# relay_driver.net
KiCad netlist of a schematic drawn in Altium Designer
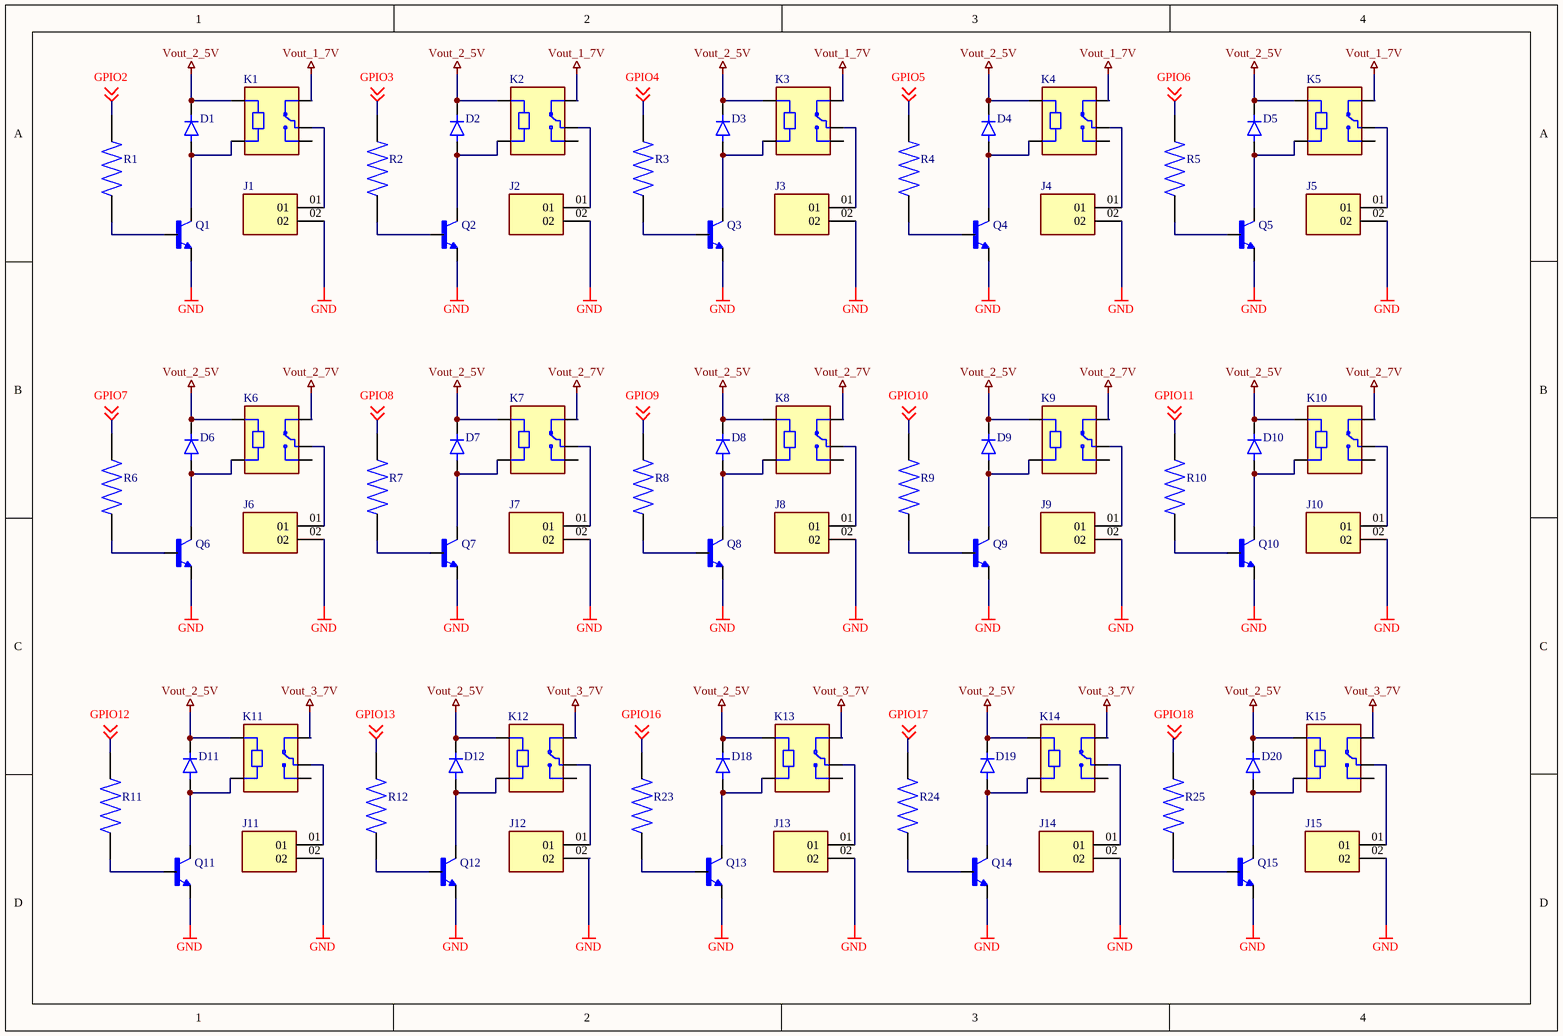
[diagram p0: relay_driver.SchDoc]

(export (version "E")
  (design (tool "Eeschema 10.0.6"))
  (components
    (comp (ref "D1")
      (value "FDLL4148")
      (footprint "DIOMELF3414N")
      (description "Diode Standard 100 V 200mA Surface Mount SOD-80")
      (fields (field (name "MF") "ON Semiconductor"))
      (libsource (lib "FDLL4148") (part "FDLL4148"))
    )
    (comp (ref "D2")
      (value "FDLL4148")
      (footprint "DIOMELF3414N")
      (description "Diode Standard 100 V 200mA Surface Mount SOD-80")
      (fields (field (name "MF") "ON Semiconductor"))
      (libsource (lib "FDLL4148") (part "FDLL4148"))
    )
    (comp (ref "D3")
      (value "FDLL4148")
      (footprint "DIOMELF3414N")
      (description "Diode Standard 100 V 200mA Surface Mount SOD-80")
      (fields (field (name "MF") "ON Semiconductor"))
      (libsource (lib "FDLL4148") (part "FDLL4148"))
    )
    (comp (ref "D4")
      (value "FDLL4148")
      (footprint "DIOMELF3414N")
      (description "Diode Standard 100 V 200mA Surface Mount SOD-80")
      (fields (field (name "MF") "ON Semiconductor"))
      (libsource (lib "FDLL4148") (part "FDLL4148"))
    )
    (comp (ref "D5")
      (value "FDLL4148")
      (footprint "DIOMELF3414N")
      (description "Diode Standard 100 V 200mA Surface Mount SOD-80")
      (fields (field (name "MF") "ON Semiconductor"))
      (libsource (lib "FDLL4148") (part "FDLL4148"))
    )
    (comp (ref "D6")
      (value "FDLL4148")
      (footprint "DIOMELF3414N")
      (description "Diode Standard 100 V 200mA Surface Mount SOD-80")
      (fields (field (name "MF") "ON Semiconductor"))
      (libsource (lib "FDLL4148") (part "FDLL4148"))
    )
    (comp (ref "D7")
      (value "FDLL4148")
      (footprint "DIOMELF3414N")
      (description "Diode Standard 100 V 200mA Surface Mount SOD-80")
      (fields (field (name "MF") "ON Semiconductor"))
      (libsource (lib "FDLL4148") (part "FDLL4148"))
    )
    (comp (ref "D8")
      (value "FDLL4148")
      (footprint "DIOMELF3414N")
      (description "Diode Standard 100 V 200mA Surface Mount SOD-80")
      (fields (field (name "MF") "ON Semiconductor"))
      (libsource (lib "FDLL4148") (part "FDLL4148"))
    )
    (comp (ref "D9")
      (value "FDLL4148")
      (footprint "DIOMELF3414N")
      (description "Diode Standard 100 V 200mA Surface Mount SOD-80")
      (fields (field (name "MF") "ON Semiconductor"))
      (libsource (lib "FDLL4148") (part "FDLL4148"))
    )
    (comp (ref "D10")
      (value "FDLL4148")
      (footprint "DIOMELF3414N")
      (description "Diode Standard 100 V 200mA Surface Mount SOD-80")
      (fields (field (name "MF") "ON Semiconductor"))
      (libsource (lib "FDLL4148") (part "FDLL4148"))
    )
    (comp (ref "D11")
      (value "FDLL4148")
      (footprint "DIOMELF3414N")
      (description "Diode Standard 100 V 200mA Surface Mount SOD-80")
      (fields (field (name "MF") "ON Semiconductor"))
      (libsource (lib "FDLL4148") (part "FDLL4148"))
    )
    (comp (ref "D12")
      (value "FDLL4148")
      (footprint "DIOMELF3414N")
      (description "Diode Standard 100 V 200mA Surface Mount SOD-80")
      (fields (field (name "MF") "ON Semiconductor"))
      (libsource (lib "FDLL4148") (part "FDLL4148"))
    )
    (comp (ref "D18")
      (value "FDLL4148")
      (footprint "DIOMELF3414N")
      (description "Diode Standard 100 V 200mA Surface Mount SOD-80")
      (fields (field (name "MF") "ON Semiconductor"))
      (libsource (lib "FDLL4148") (part "FDLL4148"))
    )
    (comp (ref "D19")
      (value "FDLL4148")
      (footprint "DIOMELF3414N")
      (description "Diode Standard 100 V 200mA Surface Mount SOD-80")
      (fields (field (name "MF") "ON Semiconductor"))
      (libsource (lib "FDLL4148") (part "FDLL4148"))
    )
    (comp (ref "D20")
      (value "FDLL4148")
      (footprint "DIOMELF3414N")
      (description "Diode Standard 100 V 200mA Surface Mount SOD-80")
      (fields (field (name "MF") "ON Semiconductor"))
      (libsource (lib "FDLL4148") (part "FDLL4148"))
    )
    (comp (ref "J1")
      (value "BBS-102-T-A")
      (footprint "SAMTEC_BBS-102-T-A")
      (fields (field (name "MF") "Samtec") (field (name "MP") "BBS102TA"))
      (libsource (lib "BBS-102-T-A") (part "BBS-102-T-A"))
    )
    (comp (ref "J2")
      (value "BBS-102-T-A")
      (footprint "SAMTEC_BBS-102-T-A")
      (fields (field (name "MF") "Samtec") (field (name "MP") "BBS102TA"))
      (libsource (lib "BBS-102-T-A") (part "BBS-102-T-A"))
    )
    (comp (ref "J3")
      (value "BBS-102-T-A")
      (footprint "SAMTEC_BBS-102-T-A")
      (fields (field (name "MF") "Samtec") (field (name "MP") "BBS102TA"))
      (libsource (lib "BBS-102-T-A") (part "BBS-102-T-A"))
    )
    (comp (ref "J4")
      (value "BBS-102-T-A")
      (footprint "SAMTEC_BBS-102-T-A")
      (fields (field (name "MF") "Samtec") (field (name "MP") "BBS102TA"))
      (libsource (lib "BBS-102-T-A") (part "BBS-102-T-A"))
    )
    (comp (ref "J5")
      (value "BBS-102-T-A")
      (footprint "SAMTEC_BBS-102-T-A")
      (fields (field (name "MF") "Samtec") (field (name "MP") "BBS102TA"))
      (libsource (lib "BBS-102-T-A") (part "BBS-102-T-A"))
    )
    (comp (ref "J6")
      (value "BBS-102-T-A")
      (footprint "SAMTEC_BBS-102-T-A")
      (fields (field (name "MF") "Samtec") (field (name "MP") "BBS102TA"))
      (libsource (lib "BBS-102-T-A") (part "BBS-102-T-A"))
    )
    (comp (ref "J7")
      (value "BBS-102-T-A")
      (footprint "SAMTEC_BBS-102-T-A")
      (fields (field (name "MF") "Samtec") (field (name "MP") "BBS102TA"))
      (libsource (lib "BBS-102-T-A") (part "BBS-102-T-A"))
    )
    (comp (ref "J8")
      (value "BBS-102-T-A")
      (footprint "SAMTEC_BBS-102-T-A")
      (fields (field (name "MF") "Samtec") (field (name "MP") "BBS102TA"))
      (libsource (lib "BBS-102-T-A") (part "BBS-102-T-A"))
    )
    (comp (ref "J9")
      (value "BBS-102-T-A")
      (footprint "SAMTEC_BBS-102-T-A")
      (fields (field (name "MF") "Samtec") (field (name "MP") "BBS102TA"))
      (libsource (lib "BBS-102-T-A") (part "BBS-102-T-A"))
    )
    (comp (ref "J10")
      (value "BBS-102-T-A")
      (footprint "SAMTEC_BBS-102-T-A")
      (fields (field (name "MF") "Samtec") (field (name "MP") "BBS102TA"))
      (libsource (lib "BBS-102-T-A") (part "BBS-102-T-A"))
    )
    (comp (ref "J11")
      (value "BBS-102-T-A")
      (footprint "SAMTEC_BBS-102-T-A")
      (fields (field (name "MF") "Samtec") (field (name "MP") "BBS102TA"))
      (libsource (lib "BBS-102-T-A") (part "BBS-102-T-A"))
    )
    (comp (ref "J12")
      (value "BBS-102-T-A")
      (footprint "SAMTEC_BBS-102-T-A")
      (fields (field (name "MF") "Samtec") (field (name "MP") "BBS102TA"))
      (libsource (lib "BBS-102-T-A") (part "BBS-102-T-A"))
    )
    (comp (ref "J13")
      (value "BBS-102-T-A")
      (footprint "SAMTEC_BBS-102-T-A")
      (fields (field (name "MF") "Samtec") (field (name "MP") "BBS102TA"))
      (libsource (lib "BBS-102-T-A") (part "BBS-102-T-A"))
    )
    (comp (ref "J14")
      (value "BBS-102-T-A")
      (footprint "SAMTEC_BBS-102-T-A")
      (fields (field (name "MF") "Samtec") (field (name "MP") "BBS102TA"))
      (libsource (lib "BBS-102-T-A") (part "BBS-102-T-A"))
    )
    (comp (ref "J15")
      (value "BBS-102-T-A")
      (footprint "SAMTEC_BBS-102-T-A")
      (fields (field (name "MF") "Samtec") (field (name "MP") "BBS102TA"))
      (libsource (lib "BBS-102-T-A") (part "BBS-102-T-A"))
    )
    (comp (ref "K1")
      (value "SRD-05VDC-SL-C")
      (footprint "RELAY_SRD-05VDC-SL-C")
      (fields (field (name "MF") "Songle Relay"))
      (libsource (lib "SRD-05VDC-SL-C") (part "SRD-05VDC-SL-C"))
    )
    (comp (ref "K2")
      (value "SRD-05VDC-SL-C")
      (footprint "RELAY_SRD-05VDC-SL-C")
      (fields (field (name "MF") "Songle Relay"))
      (libsource (lib "SRD-05VDC-SL-C") (part "SRD-05VDC-SL-C"))
    )
    (comp (ref "K3")
      (value "SRD-05VDC-SL-C")
      (footprint "RELAY_SRD-05VDC-SL-C")
      (fields (field (name "MF") "Songle Relay"))
      (libsource (lib "SRD-05VDC-SL-C") (part "SRD-05VDC-SL-C"))
    )
    (comp (ref "K4")
      (value "SRD-05VDC-SL-C")
      (footprint "RELAY_SRD-05VDC-SL-C")
      (fields (field (name "MF") "Songle Relay"))
      (libsource (lib "SRD-05VDC-SL-C") (part "SRD-05VDC-SL-C"))
    )
    (comp (ref "K5")
      (value "SRD-05VDC-SL-C")
      (footprint "RELAY_SRD-05VDC-SL-C")
      (fields (field (name "MF") "Songle Relay"))
      (libsource (lib "SRD-05VDC-SL-C") (part "SRD-05VDC-SL-C"))
    )
    (comp (ref "K6")
      (value "SRD-05VDC-SL-C")
      (footprint "RELAY_SRD-05VDC-SL-C")
      (fields (field (name "MF") "Songle Relay"))
      (libsource (lib "SRD-05VDC-SL-C") (part "SRD-05VDC-SL-C"))
    )
    (comp (ref "K7")
      (value "SRD-05VDC-SL-C")
      (footprint "RELAY_SRD-05VDC-SL-C")
      (fields (field (name "MF") "Songle Relay"))
      (libsource (lib "SRD-05VDC-SL-C") (part "SRD-05VDC-SL-C"))
    )
    (comp (ref "K8")
      (value "SRD-05VDC-SL-C")
      (footprint "RELAY_SRD-05VDC-SL-C")
      (fields (field (name "MF") "Songle Relay"))
      (libsource (lib "SRD-05VDC-SL-C") (part "SRD-05VDC-SL-C"))
    )
    (comp (ref "K9")
      (value "SRD-05VDC-SL-C")
      (footprint "RELAY_SRD-05VDC-SL-C")
      (fields (field (name "MF") "Songle Relay"))
      (libsource (lib "SRD-05VDC-SL-C") (part "SRD-05VDC-SL-C"))
    )
    (comp (ref "K10")
      (value "SRD-05VDC-SL-C")
      (footprint "RELAY_SRD-05VDC-SL-C")
      (fields (field (name "MF") "Songle Relay"))
      (libsource (lib "SRD-05VDC-SL-C") (part "SRD-05VDC-SL-C"))
    )
    (comp (ref "K11")
      (value "SRD-05VDC-SL-C")
      (footprint "RELAY_SRD-05VDC-SL-C")
      (fields (field (name "MF") "Songle Relay"))
      (libsource (lib "SRD-05VDC-SL-C") (part "SRD-05VDC-SL-C"))
    )
    (comp (ref "K12")
      (value "SRD-05VDC-SL-C")
      (footprint "RELAY_SRD-05VDC-SL-C")
      (fields (field (name "MF") "Songle Relay"))
      (libsource (lib "SRD-05VDC-SL-C") (part "SRD-05VDC-SL-C"))
    )
    (comp (ref "K13")
      (value "SRD-05VDC-SL-C")
      (footprint "RELAY_SRD-05VDC-SL-C")
      (fields (field (name "MF") "Songle Relay"))
      (libsource (lib "SRD-05VDC-SL-C") (part "SRD-05VDC-SL-C"))
    )
    (comp (ref "K14")
      (value "SRD-05VDC-SL-C")
      (footprint "RELAY_SRD-05VDC-SL-C")
      (fields (field (name "MF") "Songle Relay"))
      (libsource (lib "SRD-05VDC-SL-C") (part "SRD-05VDC-SL-C"))
    )
    (comp (ref "K15")
      (value "SRD-05VDC-SL-C")
      (footprint "RELAY_SRD-05VDC-SL-C")
      (fields (field (name "MF") "Songle Relay"))
      (libsource (lib "SRD-05VDC-SL-C") (part "SRD-05VDC-SL-C"))
    )
    (comp (ref "Q1")
      (value "BC817-40")
      (footprint "SOT95P240X120-3N")
      (description "BJT, SOT-23, 45V, 800mA, NPN, 0.31W, 150Â°C")
      (fields (field (name "MF") "Diotec Semiconductor"))
      (libsource (lib "BC817-40") (part "BC817-40"))
    )
    (comp (ref "Q2")
      (value "BC817-40")
      (footprint "SOT95P240X120-3N")
      (description "BJT, SOT-23, 45V, 800mA, NPN, 0.31W, 150Â°C")
      (fields (field (name "MF") "Diotec Semiconductor"))
      (libsource (lib "BC817-40") (part "BC817-40"))
    )
    (comp (ref "Q3")
      (value "BC817-40")
      (footprint "SOT95P240X120-3N")
      (description "BJT, SOT-23, 45V, 800mA, NPN, 0.31W, 150Â°C")
      (fields (field (name "MF") "Diotec Semiconductor"))
      (libsource (lib "BC817-40") (part "BC817-40"))
    )
    (comp (ref "Q4")
      (value "BC817-40")
      (footprint "SOT95P240X120-3N")
      (description "BJT, SOT-23, 45V, 800mA, NPN, 0.31W, 150Â°C")
      (fields (field (name "MF") "Diotec Semiconductor"))
      (libsource (lib "BC817-40") (part "BC817-40"))
    )
    (comp (ref "Q5")
      (value "BC817-40")
      (footprint "SOT95P240X120-3N")
      (description "BJT, SOT-23, 45V, 800mA, NPN, 0.31W, 150Â°C")
      (fields (field (name "MF") "Diotec Semiconductor"))
      (libsource (lib "BC817-40") (part "BC817-40"))
    )
    (comp (ref "Q6")
      (value "BC817-40")
      (footprint "SOT95P240X120-3N")
      (description "BJT, SOT-23, 45V, 800mA, NPN, 0.31W, 150Â°C")
      (fields (field (name "MF") "Diotec Semiconductor"))
      (libsource (lib "BC817-40") (part "BC817-40"))
    )
    (comp (ref "Q7")
      (value "BC817-40")
      (footprint "SOT95P240X120-3N")
      (description "BJT, SOT-23, 45V, 800mA, NPN, 0.31W, 150Â°C")
      (fields (field (name "MF") "Diotec Semiconductor"))
      (libsource (lib "BC817-40") (part "BC817-40"))
    )
    (comp (ref "Q8")
      (value "BC817-40")
      (footprint "SOT95P240X120-3N")
      (description "BJT, SOT-23, 45V, 800mA, NPN, 0.31W, 150Â°C")
      (fields (field (name "MF") "Diotec Semiconductor"))
      (libsource (lib "BC817-40") (part "BC817-40"))
    )
    (comp (ref "Q9")
      (value "BC817-40")
      (footprint "SOT95P240X120-3N")
      (description "BJT, SOT-23, 45V, 800mA, NPN, 0.31W, 150Â°C")
      (fields (field (name "MF") "Diotec Semiconductor"))
      (libsource (lib "BC817-40") (part "BC817-40"))
    )
    (comp (ref "Q10")
      (value "BC817-40")
      (footprint "SOT95P240X120-3N")
      (description "BJT, SOT-23, 45V, 800mA, NPN, 0.31W, 150Â°C")
      (fields (field (name "MF") "Diotec Semiconductor"))
      (libsource (lib "BC817-40") (part "BC817-40"))
    )
    (comp (ref "Q11")
      (value "BC817-40")
      (footprint "SOT95P240X120-3N")
      (description "BJT, SOT-23, 45V, 800mA, NPN, 0.31W, 150Â°C")
      (fields (field (name "MF") "Diotec Semiconductor"))
      (libsource (lib "BC817-40") (part "BC817-40"))
    )
    (comp (ref "Q12")
      (value "BC817-40")
      (footprint "SOT95P240X120-3N")
      (description "BJT, SOT-23, 45V, 800mA, NPN, 0.31W, 150Â°C")
      (fields (field (name "MF") "Diotec Semiconductor"))
      (libsource (lib "BC817-40") (part "BC817-40"))
    )
    (comp (ref "Q13")
      (value "BC817-40")
      (footprint "SOT95P240X120-3N")
      (description "BJT, SOT-23, 45V, 800mA, NPN, 0.31W, 150Â°C")
      (fields (field (name "MF") "Diotec Semiconductor"))
      (libsource (lib "BC817-40") (part "BC817-40"))
    )
    (comp (ref "Q14")
      (value "BC817-40")
      (footprint "SOT95P240X120-3N")
      (description "BJT, SOT-23, 45V, 800mA, NPN, 0.31W, 150Â°C")
      (fields (field (name "MF") "Diotec Semiconductor"))
      (libsource (lib "BC817-40") (part "BC817-40"))
    )
    (comp (ref "Q15")
      (value "BC817-40")
      (footprint "SOT95P240X120-3N")
      (description "BJT, SOT-23, 45V, 800mA, NPN, 0.31W, 150Â°C")
      (fields (field (name "MF") "Diotec Semiconductor"))
      (libsource (lib "BC817-40") (part "BC817-40"))
    )
    (comp (ref "R1")
      (value "ERJB3CFR15V")
      (footprint "RES_ERJB3CFR15V")
      (libsource (lib "ERJB3CFR15V") (part "ERJB3CFR15V"))
    )
    (comp (ref "R2")
      (value "ERJB3CFR15V")
      (footprint "RES_ERJB3CFR15V")
      (libsource (lib "ERJB3CFR15V") (part "ERJB3CFR15V"))
    )
    (comp (ref "R3")
      (value "ERJB3CFR15V")
      (footprint "RES_ERJB3CFR15V")
      (libsource (lib "ERJB3CFR15V") (part "ERJB3CFR15V"))
    )
    (comp (ref "R4")
      (value "ERJB3CFR15V")
      (footprint "RES_ERJB3CFR15V")
      (libsource (lib "ERJB3CFR15V") (part "ERJB3CFR15V"))
    )
    (comp (ref "R5")
      (value "ERJB3CFR15V")
      (footprint "RES_ERJB3CFR15V")
      (libsource (lib "ERJB3CFR15V") (part "ERJB3CFR15V"))
    )
    (comp (ref "R6")
      (value "ERJB3CFR15V")
      (footprint "RES_ERJB3CFR15V")
      (libsource (lib "ERJB3CFR15V") (part "ERJB3CFR15V"))
    )
    (comp (ref "R7")
      (value "ERJB3CFR15V")
      (footprint "RES_ERJB3CFR15V")
      (libsource (lib "ERJB3CFR15V") (part "ERJB3CFR15V"))
    )
    (comp (ref "R8")
      (value "ERJB3CFR15V")
      (footprint "RES_ERJB3CFR15V")
      (libsource (lib "ERJB3CFR15V") (part "ERJB3CFR15V"))
    )
    (comp (ref "R9")
      (value "ERJB3CFR15V")
      (footprint "RES_ERJB3CFR15V")
      (libsource (lib "ERJB3CFR15V") (part "ERJB3CFR15V"))
    )
    (comp (ref "R10")
      (value "ERJB3CFR15V")
      (footprint "RES_ERJB3CFR15V")
      (libsource (lib "ERJB3CFR15V") (part "ERJB3CFR15V"))
    )
    (comp (ref "R11")
      (value "ERJB3CFR15V")
      (footprint "RES_ERJB3CFR15V")
      (libsource (lib "ERJB3CFR15V") (part "ERJB3CFR15V"))
    )
    (comp (ref "R12")
      (value "ERJB3CFR15V")
      (footprint "RES_ERJB3CFR15V")
      (libsource (lib "ERJB3CFR15V") (part "ERJB3CFR15V"))
    )
    (comp (ref "R23")
      (value "ERJB3CFR15V")
      (footprint "RES_ERJB3CFR15V")
      (libsource (lib "ERJB3CFR15V") (part "ERJB3CFR15V"))
    )
    (comp (ref "R24")
      (value "ERJB3CFR15V")
      (footprint "RES_ERJB3CFR15V")
      (libsource (lib "ERJB3CFR15V") (part "ERJB3CFR15V"))
    )
    (comp (ref "R25")
      (value "ERJB3CFR15V")
      (footprint "RES_ERJB3CFR15V")
      (libsource (lib "ERJB3CFR15V") (part "ERJB3CFR15V"))
    )
  )
  (nets
    (net (code "1") (name "GND") (class "Default")
      (node (ref "J1") (pin "02") (pinfunction "02_02") (pintype "passive"))
      (node (ref "J10") (pin "02") (pinfunction "02_02") (pintype "passive"))
      (node (ref "J11") (pin "02") (pinfunction "02_02") (pintype "passive"))
      (node (ref "J12") (pin "02") (pinfunction "02_02") (pintype "passive"))
      (node (ref "J13") (pin "02") (pinfunction "02_02") (pintype "passive"))
      (node (ref "J14") (pin "02") (pinfunction "02_02") (pintype "passive"))
      (node (ref "J15") (pin "02") (pinfunction "02_02") (pintype "passive"))
      (node (ref "J2") (pin "02") (pinfunction "02_02") (pintype "passive"))
      (node (ref "J3") (pin "02") (pinfunction "02_02") (pintype "passive"))
      (node (ref "J4") (pin "02") (pinfunction "02_02") (pintype "passive"))
      (node (ref "J5") (pin "02") (pinfunction "02_02") (pintype "passive"))
      (node (ref "J6") (pin "02") (pinfunction "02_02") (pintype "passive"))
      (node (ref "J7") (pin "02") (pinfunction "02_02") (pintype "passive"))
      (node (ref "J8") (pin "02") (pinfunction "02_02") (pintype "passive"))
      (node (ref "J9") (pin "02") (pinfunction "02_02") (pintype "passive"))
      (node (ref "Q1") (pin "2") (pinfunction "E_2") (pintype "passive"))
      (node (ref "Q10") (pin "2") (pinfunction "E_2") (pintype "passive"))
      (node (ref "Q11") (pin "2") (pinfunction "E_2") (pintype "passive"))
      (node (ref "Q12") (pin "2") (pinfunction "E_2") (pintype "passive"))
      (node (ref "Q13") (pin "2") (pinfunction "E_2") (pintype "passive"))
      (node (ref "Q14") (pin "2") (pinfunction "E_2") (pintype "passive"))
      (node (ref "Q15") (pin "2") (pinfunction "E_2") (pintype "passive"))
      (node (ref "Q2") (pin "2") (pinfunction "E_2") (pintype "passive"))
      (node (ref "Q3") (pin "2") (pinfunction "E_2") (pintype "passive"))
      (node (ref "Q4") (pin "2") (pinfunction "E_2") (pintype "passive"))
      (node (ref "Q5") (pin "2") (pinfunction "E_2") (pintype "passive"))
      (node (ref "Q6") (pin "2") (pinfunction "E_2") (pintype "passive"))
      (node (ref "Q7") (pin "2") (pinfunction "E_2") (pintype "passive"))
      (node (ref "Q8") (pin "2") (pinfunction "E_2") (pintype "passive"))
      (node (ref "Q9") (pin "2") (pinfunction "E_2") (pintype "passive"))
    )
    (net (code "2") (name "GPIO2") (class "Default")
      (node (ref "R1") (pin "2") (pinfunction "2_2") (pintype "passive"))
    )
    (net (code "3") (name "GPIO3") (class "Default")
      (node (ref "R2") (pin "2") (pinfunction "2_2") (pintype "passive"))
    )
    (net (code "4") (name "GPIO4") (class "Default")
      (node (ref "R3") (pin "2") (pinfunction "2_2") (pintype "passive"))
    )
    (net (code "5") (name "GPIO5") (class "Default")
      (node (ref "R4") (pin "2") (pinfunction "2_2") (pintype "passive"))
    )
    (net (code "6") (name "GPIO6") (class "Default")
      (node (ref "R5") (pin "2") (pinfunction "2_2") (pintype "passive"))
    )
    (net (code "7") (name "GPIO7") (class "Default")
      (node (ref "R6") (pin "2") (pinfunction "2_2") (pintype "passive"))
    )
    (net (code "8") (name "GPIO8") (class "Default")
      (node (ref "R7") (pin "2") (pinfunction "2_2") (pintype "passive"))
    )
    (net (code "9") (name "GPIO9") (class "Default")
      (node (ref "R8") (pin "2") (pinfunction "2_2") (pintype "passive"))
    )
    (net (code "10") (name "GPIO10") (class "Default")
      (node (ref "R9") (pin "2") (pinfunction "2_2") (pintype "passive"))
    )
    (net (code "11") (name "GPIO11") (class "Default")
      (node (ref "R10") (pin "2") (pinfunction "2_2") (pintype "passive"))
    )
    (net (code "12") (name "GPIO12") (class "Default")
      (node (ref "R11") (pin "2") (pinfunction "2_2") (pintype "passive"))
    )
    (net (code "13") (name "GPIO13") (class "Default")
      (node (ref "R12") (pin "2") (pinfunction "2_2") (pintype "passive"))
    )
    (net (code "14") (name "GPIO16") (class "Default")
      (node (ref "R23") (pin "2") (pinfunction "2_2") (pintype "passive"))
    )
    (net (code "15") (name "GPIO17") (class "Default")
      (node (ref "R24") (pin "2") (pinfunction "2_2") (pintype "passive"))
    )
    (net (code "16") (name "GPIO18") (class "Default")
      (node (ref "R25") (pin "2") (pinfunction "2_2") (pintype "passive"))
    )
    (net (code "17") (name "Net-(J1-Pad01)") (class "Default")
      (node (ref "J1") (pin "01") (pinfunction "01_01") (pintype "passive"))
      (node (ref "K1") (pin "COM") (pinfunction "COM_COM") (pintype "passive"))
    )
    (net (code "18") (name "Net-(J2-Pad01)") (class "Default")
      (node (ref "J2") (pin "01") (pinfunction "01_01") (pintype "passive"))
      (node (ref "K2") (pin "COM") (pinfunction "COM_COM") (pintype "passive"))
    )
    (net (code "19") (name "Net-(J3-Pad01)") (class "Default")
      (node (ref "J3") (pin "01") (pinfunction "01_01") (pintype "passive"))
      (node (ref "K3") (pin "COM") (pinfunction "COM_COM") (pintype "passive"))
    )
    (net (code "20") (name "Net-(J4-Pad01)") (class "Default")
      (node (ref "J4") (pin "01") (pinfunction "01_01") (pintype "passive"))
      (node (ref "K4") (pin "COM") (pinfunction "COM_COM") (pintype "passive"))
    )
    (net (code "21") (name "Net-(J5-Pad01)") (class "Default")
      (node (ref "J5") (pin "01") (pinfunction "01_01") (pintype "passive"))
      (node (ref "K5") (pin "COM") (pinfunction "COM_COM") (pintype "passive"))
    )
    (net (code "22") (name "Net-(J6-Pad01)") (class "Default")
      (node (ref "J6") (pin "01") (pinfunction "01_01") (pintype "passive"))
      (node (ref "K6") (pin "COM") (pinfunction "COM_COM") (pintype "passive"))
    )
    (net (code "23") (name "Net-(J7-Pad01)") (class "Default")
      (node (ref "J7") (pin "01") (pinfunction "01_01") (pintype "passive"))
      (node (ref "K7") (pin "COM") (pinfunction "COM_COM") (pintype "passive"))
    )
    (net (code "24") (name "Net-(J8-Pad01)") (class "Default")
      (node (ref "J8") (pin "01") (pinfunction "01_01") (pintype "passive"))
      (node (ref "K8") (pin "COM") (pinfunction "COM_COM") (pintype "passive"))
    )
    (net (code "25") (name "Net-(J9-Pad01)") (class "Default")
      (node (ref "J9") (pin "01") (pinfunction "01_01") (pintype "passive"))
      (node (ref "K9") (pin "COM") (pinfunction "COM_COM") (pintype "passive"))
    )
    (net (code "26") (name "Net-(J10-Pad01)") (class "Default")
      (node (ref "J10") (pin "01") (pinfunction "01_01") (pintype "passive"))
      (node (ref "K10") (pin "COM") (pinfunction "COM_COM") (pintype "passive"))
    )
    (net (code "27") (name "Net-(J11-Pad01)") (class "Default")
      (node (ref "J11") (pin "01") (pinfunction "01_01") (pintype "passive"))
      (node (ref "K11") (pin "COM") (pinfunction "COM_COM") (pintype "passive"))
    )
    (net (code "28") (name "Net-(J12-Pad01)") (class "Default")
      (node (ref "J12") (pin "01") (pinfunction "01_01") (pintype "passive"))
      (node (ref "K12") (pin "COM") (pinfunction "COM_COM") (pintype "passive"))
    )
    (net (code "29") (name "Net-(J13-Pad01)") (class "Default")
      (node (ref "J13") (pin "01") (pinfunction "01_01") (pintype "passive"))
      (node (ref "K13") (pin "COM") (pinfunction "COM_COM") (pintype "passive"))
    )
    (net (code "30") (name "Net-(J14-Pad01)") (class "Default")
      (node (ref "J14") (pin "01") (pinfunction "01_01") (pintype "passive"))
      (node (ref "K14") (pin "COM") (pinfunction "COM_COM") (pintype "passive"))
    )
    (net (code "31") (name "Net-(J15-Pad01)") (class "Default")
      (node (ref "J15") (pin "01") (pinfunction "01_01") (pintype "passive"))
      (node (ref "K15") (pin "COM") (pinfunction "COM_COM") (pintype "passive"))
    )
    (net (code "32") (name "Net-(Q1-B)") (class "Default")
      (node (ref "Q1") (pin "1") (pinfunction "B_1") (pintype "passive"))
      (node (ref "R1") (pin "1") (pinfunction "1_1") (pintype "passive"))
    )
    (net (code "33") (name "Net-(Q1-C)") (class "Default")
      (node (ref "D1") (pin "A") (pinfunction "A_A") (pintype "passive"))
      (node (ref "K1") (pin "A1") (pinfunction "A1_A1") (pintype "passive"))
      (node (ref "Q1") (pin "3") (pinfunction "C_3") (pintype "passive"))
    )
    (net (code "34") (name "Net-(Q2-B)") (class "Default")
      (node (ref "Q2") (pin "1") (pinfunction "B_1") (pintype "passive"))
      (node (ref "R2") (pin "1") (pinfunction "1_1") (pintype "passive"))
    )
    (net (code "35") (name "Net-(Q2-C)") (class "Default")
      (node (ref "D2") (pin "A") (pinfunction "A_A") (pintype "passive"))
      (node (ref "K2") (pin "A1") (pinfunction "A1_A1") (pintype "passive"))
      (node (ref "Q2") (pin "3") (pinfunction "C_3") (pintype "passive"))
    )
    (net (code "36") (name "Net-(Q3-B)") (class "Default")
      (node (ref "Q3") (pin "1") (pinfunction "B_1") (pintype "passive"))
      (node (ref "R3") (pin "1") (pinfunction "1_1") (pintype "passive"))
    )
    (net (code "37") (name "Net-(Q3-C)") (class "Default")
      (node (ref "D3") (pin "A") (pinfunction "A_A") (pintype "passive"))
      (node (ref "K3") (pin "A1") (pinfunction "A1_A1") (pintype "passive"))
      (node (ref "Q3") (pin "3") (pinfunction "C_3") (pintype "passive"))
    )
    (net (code "38") (name "Net-(Q4-B)") (class "Default")
      (node (ref "Q4") (pin "1") (pinfunction "B_1") (pintype "passive"))
      (node (ref "R4") (pin "1") (pinfunction "1_1") (pintype "passive"))
    )
    (net (code "39") (name "Net-(Q4-C)") (class "Default")
      (node (ref "D4") (pin "A") (pinfunction "A_A") (pintype "passive"))
      (node (ref "K4") (pin "A1") (pinfunction "A1_A1") (pintype "passive"))
      (node (ref "Q4") (pin "3") (pinfunction "C_3") (pintype "passive"))
    )
    (net (code "40") (name "Net-(Q5-B)") (class "Default")
      (node (ref "Q5") (pin "1") (pinfunction "B_1") (pintype "passive"))
      (node (ref "R5") (pin "1") (pinfunction "1_1") (pintype "passive"))
    )
    (net (code "41") (name "Net-(Q5-C)") (class "Default")
      (node (ref "D5") (pin "A") (pinfunction "A_A") (pintype "passive"))
      (node (ref "K5") (pin "A1") (pinfunction "A1_A1") (pintype "passive"))
      (node (ref "Q5") (pin "3") (pinfunction "C_3") (pintype "passive"))
    )
    (net (code "42") (name "Net-(Q6-B)") (class "Default")
      (node (ref "Q6") (pin "1") (pinfunction "B_1") (pintype "passive"))
      (node (ref "R6") (pin "1") (pinfunction "1_1") (pintype "passive"))
    )
    (net (code "43") (name "Net-(Q6-C)") (class "Default")
      (node (ref "D6") (pin "A") (pinfunction "A_A") (pintype "passive"))
      (node (ref "K6") (pin "A1") (pinfunction "A1_A1") (pintype "passive"))
      (node (ref "Q6") (pin "3") (pinfunction "C_3") (pintype "passive"))
    )
    (net (code "44") (name "Net-(Q7-B)") (class "Default")
      (node (ref "Q7") (pin "1") (pinfunction "B_1") (pintype "passive"))
      (node (ref "R7") (pin "1") (pinfunction "1_1") (pintype "passive"))
    )
    (net (code "45") (name "Net-(Q7-C)") (class "Default")
      (node (ref "D7") (pin "A") (pinfunction "A_A") (pintype "passive"))
      (node (ref "K7") (pin "A1") (pinfunction "A1_A1") (pintype "passive"))
      (node (ref "Q7") (pin "3") (pinfunction "C_3") (pintype "passive"))
    )
    (net (code "46") (name "Net-(Q8-B)") (class "Default")
      (node (ref "Q8") (pin "1") (pinfunction "B_1") (pintype "passive"))
      (node (ref "R8") (pin "1") (pinfunction "1_1") (pintype "passive"))
    )
    (net (code "47") (name "Net-(Q8-C)") (class "Default")
      (node (ref "D8") (pin "A") (pinfunction "A_A") (pintype "passive"))
      (node (ref "K8") (pin "A1") (pinfunction "A1_A1") (pintype "passive"))
      (node (ref "Q8") (pin "3") (pinfunction "C_3") (pintype "passive"))
    )
    (net (code "48") (name "Net-(Q9-B)") (class "Default")
      (node (ref "Q9") (pin "1") (pinfunction "B_1") (pintype "passive"))
      (node (ref "R9") (pin "1") (pinfunction "1_1") (pintype "passive"))
    )
    (net (code "49") (name "Net-(Q9-C)") (class "Default")
      (node (ref "D9") (pin "A") (pinfunction "A_A") (pintype "passive"))
      (node (ref "K9") (pin "A1") (pinfunction "A1_A1") (pintype "passive"))
      (node (ref "Q9") (pin "3") (pinfunction "C_3") (pintype "passive"))
    )
    (net (code "50") (name "Net-(Q10-B)") (class "Default")
      (node (ref "Q10") (pin "1") (pinfunction "B_1") (pintype "passive"))
      (node (ref "R10") (pin "1") (pinfunction "1_1") (pintype "passive"))
    )
    (net (code "51") (name "Net-(Q10-C)") (class "Default")
      (node (ref "D10") (pin "A") (pinfunction "A_A") (pintype "passive"))
      (node (ref "K10") (pin "A1") (pinfunction "A1_A1") (pintype "passive"))
      (node (ref "Q10") (pin "3") (pinfunction "C_3") (pintype "passive"))
    )
    (net (code "52") (name "Net-(Q11-B)") (class "Default")
      (node (ref "Q11") (pin "1") (pinfunction "B_1") (pintype "passive"))
      (node (ref "R11") (pin "1") (pinfunction "1_1") (pintype "passive"))
    )
    (net (code "53") (name "Net-(Q11-C)") (class "Default")
      (node (ref "D11") (pin "A") (pinfunction "A_A") (pintype "passive"))
      (node (ref "K11") (pin "A1") (pinfunction "A1_A1") (pintype "passive"))
      (node (ref "Q11") (pin "3") (pinfunction "C_3") (pintype "passive"))
    )
    (net (code "54") (name "Net-(Q12-B)") (class "Default")
      (node (ref "Q12") (pin "1") (pinfunction "B_1") (pintype "passive"))
      (node (ref "R12") (pin "1") (pinfunction "1_1") (pintype "passive"))
    )
    (net (code "55") (name "Net-(Q12-C)") (class "Default")
      (node (ref "D12") (pin "A") (pinfunction "A_A") (pintype "passive"))
      (node (ref "K12") (pin "A1") (pinfunction "A1_A1") (pintype "passive"))
      (node (ref "Q12") (pin "3") (pinfunction "C_3") (pintype "passive"))
    )
    (net (code "56") (name "Net-(Q13-B)") (class "Default")
      (node (ref "Q13") (pin "1") (pinfunction "B_1") (pintype "passive"))
      (node (ref "R23") (pin "1") (pinfunction "1_1") (pintype "passive"))
    )
    (net (code "57") (name "Net-(Q13-C)") (class "Default")
      (node (ref "D18") (pin "A") (pinfunction "A_A") (pintype "passive"))
      (node (ref "K13") (pin "A1") (pinfunction "A1_A1") (pintype "passive"))
      (node (ref "Q13") (pin "3") (pinfunction "C_3") (pintype "passive"))
    )
    (net (code "58") (name "Net-(Q14-B)") (class "Default")
      (node (ref "Q14") (pin "1") (pinfunction "B_1") (pintype "passive"))
      (node (ref "R24") (pin "1") (pinfunction "1_1") (pintype "passive"))
    )
    (net (code "59") (name "Net-(Q14-C)") (class "Default")
      (node (ref "D19") (pin "A") (pinfunction "A_A") (pintype "passive"))
      (node (ref "K14") (pin "A1") (pinfunction "A1_A1") (pintype "passive"))
      (node (ref "Q14") (pin "3") (pinfunction "C_3") (pintype "passive"))
    )
    (net (code "60") (name "Net-(Q15-B)") (class "Default")
      (node (ref "Q15") (pin "1") (pinfunction "B_1") (pintype "passive"))
      (node (ref "R25") (pin "1") (pinfunction "1_1") (pintype "passive"))
    )
    (net (code "61") (name "Net-(Q15-C)") (class "Default")
      (node (ref "D20") (pin "A") (pinfunction "A_A") (pintype "passive"))
      (node (ref "K15") (pin "A1") (pinfunction "A1_A1") (pintype "passive"))
      (node (ref "Q15") (pin "3") (pinfunction "C_3") (pintype "passive"))
    )
    (net (code "62") (name "Vout_1_7V") (class "Default")
      (node (ref "K1") (pin "NC") (pinfunction "NC_NC") (pintype "passive"))
      (node (ref "K2") (pin "NC") (pinfunction "NC_NC") (pintype "passive"))
      (node (ref "K3") (pin "NC") (pinfunction "NC_NC") (pintype "passive"))
      (node (ref "K4") (pin "NC") (pinfunction "NC_NC") (pintype "passive"))
      (node (ref "K5") (pin "NC") (pinfunction "NC_NC") (pintype "passive"))
    )
    (net (code "63") (name "Vout_2_5V") (class "Default")
      (node (ref "D1") (pin "C") (pinfunction "C_C") (pintype "passive"))
      (node (ref "D10") (pin "C") (pinfunction "C_C") (pintype "passive"))
      (node (ref "D11") (pin "C") (pinfunction "C_C") (pintype "passive"))
      (node (ref "D12") (pin "C") (pinfunction "C_C") (pintype "passive"))
      (node (ref "D18") (pin "C") (pinfunction "C_C") (pintype "passive"))
      (node (ref "D19") (pin "C") (pinfunction "C_C") (pintype "passive"))
      (node (ref "D2") (pin "C") (pinfunction "C_C") (pintype "passive"))
      (node (ref "D20") (pin "C") (pinfunction "C_C") (pintype "passive"))
      (node (ref "D3") (pin "C") (pinfunction "C_C") (pintype "passive"))
      (node (ref "D4") (pin "C") (pinfunction "C_C") (pintype "passive"))
      (node (ref "D5") (pin "C") (pinfunction "C_C") (pintype "passive"))
      (node (ref "D6") (pin "C") (pinfunction "C_C") (pintype "passive"))
      (node (ref "D7") (pin "C") (pinfunction "C_C") (pintype "passive"))
      (node (ref "D8") (pin "C") (pinfunction "C_C") (pintype "passive"))
      (node (ref "D9") (pin "C") (pinfunction "C_C") (pintype "passive"))
      (node (ref "K1") (pin "A2") (pinfunction "A2_A2") (pintype "passive"))
      (node (ref "K10") (pin "A2") (pinfunction "A2_A2") (pintype "passive"))
      (node (ref "K11") (pin "A2") (pinfunction "A2_A2") (pintype "passive"))
      (node (ref "K12") (pin "A2") (pinfunction "A2_A2") (pintype "passive"))
      (node (ref "K13") (pin "A2") (pinfunction "A2_A2") (pintype "passive"))
      (node (ref "K14") (pin "A2") (pinfunction "A2_A2") (pintype "passive"))
      (node (ref "K15") (pin "A2") (pinfunction "A2_A2") (pintype "passive"))
      (node (ref "K2") (pin "A2") (pinfunction "A2_A2") (pintype "passive"))
      (node (ref "K3") (pin "A2") (pinfunction "A2_A2") (pintype "passive"))
      (node (ref "K4") (pin "A2") (pinfunction "A2_A2") (pintype "passive"))
      (node (ref "K5") (pin "A2") (pinfunction "A2_A2") (pintype "passive"))
      (node (ref "K6") (pin "A2") (pinfunction "A2_A2") (pintype "passive"))
      (node (ref "K7") (pin "A2") (pinfunction "A2_A2") (pintype "passive"))
      (node (ref "K8") (pin "A2") (pinfunction "A2_A2") (pintype "passive"))
      (node (ref "K9") (pin "A2") (pinfunction "A2_A2") (pintype "passive"))
    )
    (net (code "64") (name "Vout_2_7V") (class "Default")
      (node (ref "K10") (pin "NC") (pinfunction "NC_NC") (pintype "passive"))
      (node (ref "K6") (pin "NC") (pinfunction "NC_NC") (pintype "passive"))
      (node (ref "K7") (pin "NC") (pinfunction "NC_NC") (pintype "passive"))
      (node (ref "K8") (pin "NC") (pinfunction "NC_NC") (pintype "passive"))
      (node (ref "K9") (pin "NC") (pinfunction "NC_NC") (pintype "passive"))
    )
    (net (code "65") (name "Vout_3_7V") (class "Default")
      (node (ref "K11") (pin "NC") (pinfunction "NC_NC") (pintype "passive"))
      (node (ref "K12") (pin "NC") (pinfunction "NC_NC") (pintype "passive"))
      (node (ref "K13") (pin "NC") (pinfunction "NC_NC") (pintype "passive"))
      (node (ref "K14") (pin "NC") (pinfunction "NC_NC") (pintype "passive"))
      (node (ref "K15") (pin "NC") (pinfunction "NC_NC") (pintype "passive"))
    )
    (net (code "66") (name "unconnected-(K1-PadNO)") (class "Default")
      (node (ref "K1") (pin "NO") (pinfunction "NO_NO") (pintype "passive"))
    )
    (net (code "67") (name "unconnected-(K2-PadNO)") (class "Default")
      (node (ref "K2") (pin "NO") (pinfunction "NO_NO") (pintype "passive"))
    )
    (net (code "68") (name "unconnected-(K3-PadNO)") (class "Default")
      (node (ref "K3") (pin "NO") (pinfunction "NO_NO") (pintype "passive"))
    )
    (net (code "69") (name "unconnected-(K4-PadNO)") (class "Default")
      (node (ref "K4") (pin "NO") (pinfunction "NO_NO") (pintype "passive"))
    )
    (net (code "70") (name "unconnected-(K5-PadNO)") (class "Default")
      (node (ref "K5") (pin "NO") (pinfunction "NO_NO") (pintype "passive"))
    )
    (net (code "71") (name "unconnected-(K6-PadNO)") (class "Default")
      (node (ref "K6") (pin "NO") (pinfunction "NO_NO") (pintype "passive"))
    )
    (net (code "72") (name "unconnected-(K7-PadNO)") (class "Default")
      (node (ref "K7") (pin "NO") (pinfunction "NO_NO") (pintype "passive"))
    )
    (net (code "73") (name "unconnected-(K8-PadNO)") (class "Default")
      (node (ref "K8") (pin "NO") (pinfunction "NO_NO") (pintype "passive"))
    )
    (net (code "74") (name "unconnected-(K9-PadNO)") (class "Default")
      (node (ref "K9") (pin "NO") (pinfunction "NO_NO") (pintype "passive"))
    )
    (net (code "75") (name "unconnected-(K10-PadNO)") (class "Default")
      (node (ref "K10") (pin "NO") (pinfunction "NO_NO") (pintype "passive"))
    )
    (net (code "76") (name "unconnected-(K11-PadNO)") (class "Default")
      (node (ref "K11") (pin "NO") (pinfunction "NO_NO") (pintype "passive"))
    )
    (net (code "77") (name "unconnected-(K12-PadNO)") (class "Default")
      (node (ref "K12") (pin "NO") (pinfunction "NO_NO") (pintype "passive"))
    )
    (net (code "78") (name "unconnected-(K13-PadNO)") (class "Default")
      (node (ref "K13") (pin "NO") (pinfunction "NO_NO") (pintype "passive"))
    )
    (net (code "79") (name "unconnected-(K14-PadNO)") (class "Default")
      (node (ref "K14") (pin "NO") (pinfunction "NO_NO") (pintype "passive"))
    )
    (net (code "80") (name "unconnected-(K15-PadNO)") (class "Default")
      (node (ref "K15") (pin "NO") (pinfunction "NO_NO") (pintype "passive"))
    )
  )
)
